# MCU.net
KiCad netlist of a schematic drawn in Altium Designer
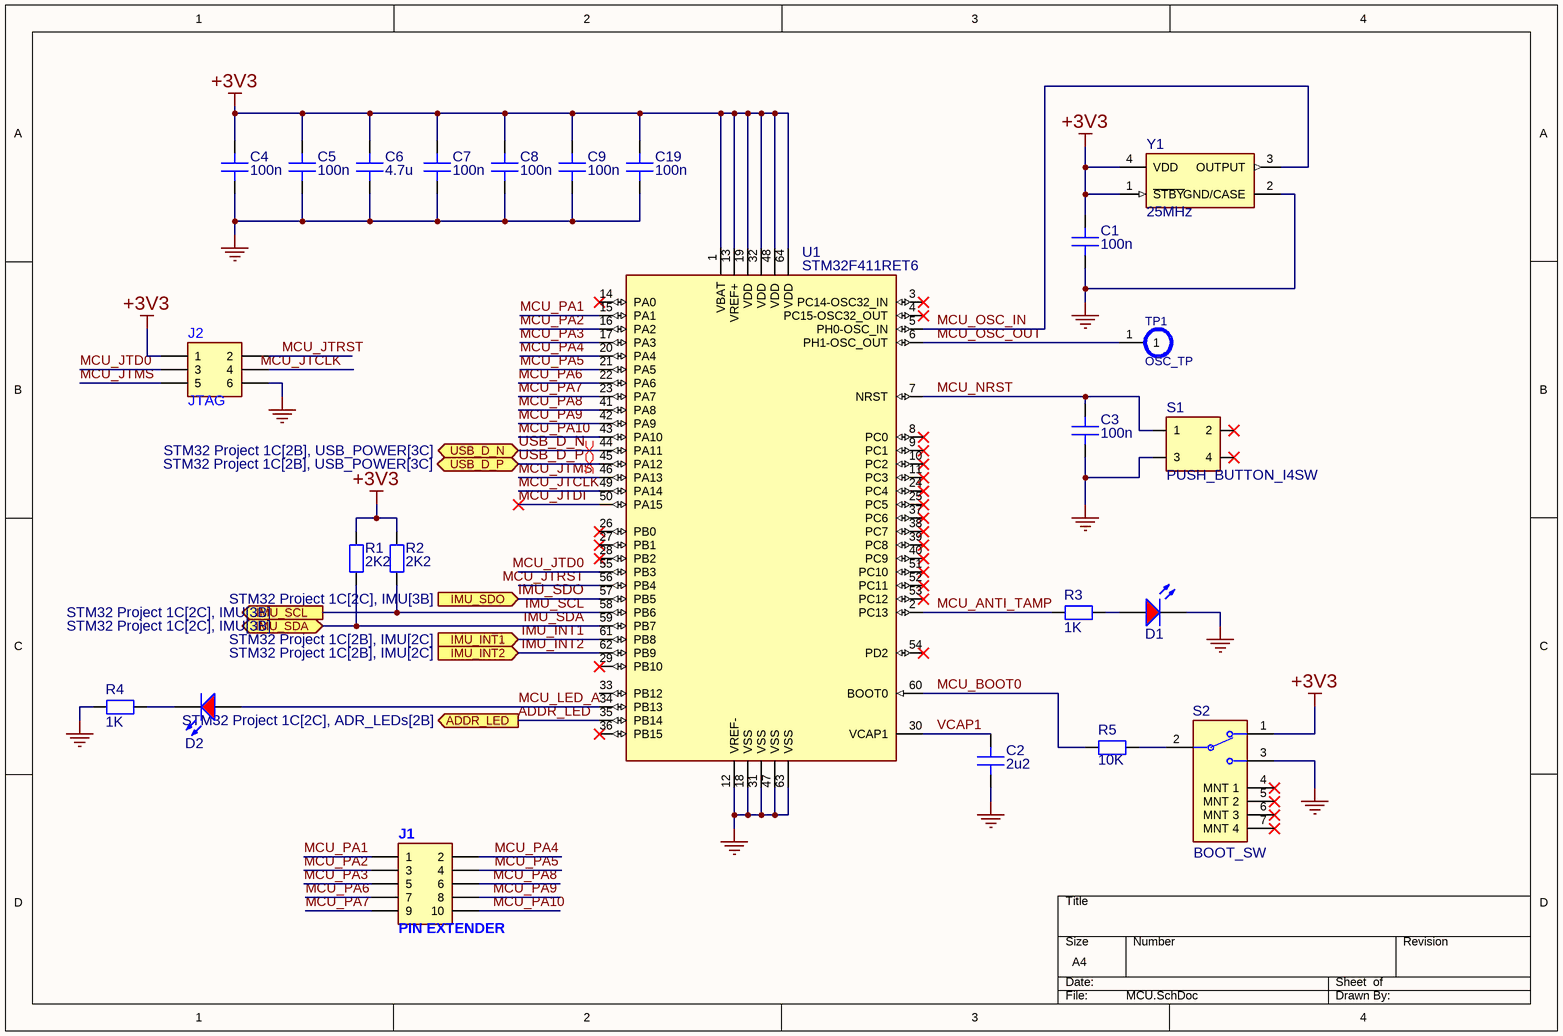
[diagram p0: MCU.SchDoc]

(export (version "E")
  (design (tool "Eeschema 10.0.6"))
  (components
    (comp (ref "C1")
      (value "100n")
      (footprint "CAP_0805")
      (description "Capacitor SMD 0805 Generic")
      (libsource (lib "Generic-Schematic-Library") (part "CAP_0805"))
    )
    (comp (ref "C2")
      (value "2u2")
      (footprint "CAP_0805")
      (description "Capacitor SMD 0805 Generic")
      (libsource (lib "Generic-Schematic-Library") (part "CAP_0805"))
    )
    (comp (ref "C3")
      (value "100n")
      (footprint "CAP_0805")
      (description "Capacitor SMD 0805 Generic")
      (libsource (lib "Generic-Schematic-Library") (part "CAP_0805"))
    )
    (comp (ref "C4")
      (value "100n")
      (footprint "CAP_0805")
      (description "Capacitor SMD 0805 Generic")
      (libsource (lib "Generic-Schematic-Library") (part "CAP_0805"))
    )
    (comp (ref "C5")
      (value "100n")
      (footprint "CAP_0805")
      (description "Capacitor SMD 0805 Generic")
      (libsource (lib "Generic-Schematic-Library") (part "CAP_0805"))
    )
    (comp (ref "C6")
      (value "4.7u")
      (footprint "CAP_0805")
      (description "Capacitor SMD 0805 Generic")
      (libsource (lib "Generic-Schematic-Library") (part "CAP_0805"))
    )
    (comp (ref "C7")
      (value "100n")
      (footprint "CAP_0805")
      (description "Capacitor SMD 0805 Generic")
      (libsource (lib "Generic-Schematic-Library") (part "CAP_0805"))
    )
    (comp (ref "C8")
      (value "100n")
      (footprint "CAP_0805")
      (description "Capacitor SMD 0805 Generic")
      (libsource (lib "Generic-Schematic-Library") (part "CAP_0805"))
    )
    (comp (ref "C9")
      (value "100n")
      (footprint "CAP_0805")
      (description "Capacitor SMD 0805 Generic")
      (libsource (lib "Generic-Schematic-Library") (part "CAP_0805"))
    )
    (comp (ref "C19")
      (value "100n")
      (footprint "CAP_0805")
      (description "Capacitor SMD 0805 Generic")
      (libsource (lib "Generic-Schematic-Library") (part "CAP_0805"))
    )
    (comp (ref "D1")
      (value "LED_RED_0805")
      (footprint "LED_RED_0805")
      (description "Chip LED, Green, 2.2 V, -40 to 85 degC, 2-Pin SMD, Pb-Free, Tape and Reel")
      (libsource (lib "Generic-Schematic-Library") (part "LED_RED_0805"))
    )
    (comp (ref "D2")
      (value "LED_RED_0805")
      (footprint "LED_RED_0805")
      (description "Chip LED, Green, 2.2 V, -40 to 85 degC, 2-Pin SMD, Pb-Free, Tape and Reel")
      (libsource (lib "Generic-Schematic-Library") (part "LED_RED_0805"))
    )
    (comp (ref "J1")
      (value "PIN EXTENDER")
      (footprint "10P_2x5_HEADER")
      (description "10 Position SMD Pin Header 2x5")
      (libsource (lib "Generic-Schematic-Library") (part "10P_2x5_HEADER"))
    )
    (comp (ref "J2")
      (value "JTAG")
      (footprint "6P_2x3_HEADER")
      (description "Male Header, Pitch 2.54 mm, 2 x 3 Position, Height 8.13 mm, -65 to 125 degC, RoHS, Tube")
      (libsource (lib "Generic-Schematic-Library") (part "6P_2x3_HEADER"))
    )
    (comp (ref "R1")
      (value "2K2")
      (footprint "RES_0805")
      (description "Resistor SMD 0805 Generic")
      (libsource (lib "Generic-Schematic-Library") (part "RES_0805"))
    )
    (comp (ref "R2")
      (value "2K2")
      (footprint "RES_0805")
      (description "Resistor SMD 0805 Generic")
      (libsource (lib "Generic-Schematic-Library") (part "RES_0805"))
    )
    (comp (ref "R3")
      (value "1K")
      (footprint "RES_0805")
      (description "Resistor SMD 0805 Generic")
      (libsource (lib "Generic-Schematic-Library") (part "RES_0805"))
    )
    (comp (ref "R4")
      (value "1K")
      (footprint "RES_0805")
      (description "Resistor SMD 0805 Generic")
      (libsource (lib "Generic-Schematic-Library") (part "RES_0805"))
    )
    (comp (ref "R5")
      (value "10K")
      (footprint "RES_0805")
      (description "Resistor SMD 0805 Generic")
      (libsource (lib "Generic-Schematic-Library") (part "RES_0805"))
    )
    (comp (ref "S1")
      (value "PUSH_BUTTON_I4SW")
      (footprint "PUSH_BUTTON_I4SW")
      (libsource (lib "Generic-Schematic-Library") (part "PUSH_BUTTON_I4SW"))
    )
    (comp (ref "S2")
      (value "BOOT_SW")
      (footprint "SLIDE_SWITCH_SPDT")
      (description "SWITCH SLIDE SPDT 300MA 6V")
      (libsource (lib "Generic-Schematic-Library") (part "SLIDE_SWITCH_SPDT"))
    )
    (comp (ref "TP1")
      (value "OSC_TP")
      (footprint "TEST_POINT_SMD")
      (description "Test Point SMD Generic - for in circuit test")
      (libsource (lib "Generic-Schematic-Library") (part "TEST_POINT_SMD"))
    )
    (comp (ref "U1")
      (value "STM32F411RET6")
      (footprint "STM32F411RET6")
      (libsource (lib "Generic-Schematic-Library") (part "STM32F411RET6"))
    )
    (comp (ref "Y1")
      (value "25MHz")
      (footprint "XTAL_OSCILLATOR_25MHz")
      (description "XTAL Oscillator 25MHz ±50ppm CMOS 3.3V 4-SMD 3.2mm x 2.5mm")
      (libsource (lib "Generic-Schematic-Library") (part "XTAL_OSCILLATOR_25MHz"))
    )
  )
  (nets
    (net (code "1") (name "+3V3") (class "Default")
      (node (ref "C1") (pin "2") (pintype "passive"))
      (node (ref "C19") (pin "2") (pintype "passive"))
      (node (ref "C4") (pin "2") (pintype "passive"))
      (node (ref "C5") (pin "2") (pintype "passive"))
      (node (ref "C6") (pin "2") (pintype "passive"))
      (node (ref "C7") (pin "2") (pintype "passive"))
      (node (ref "C8") (pin "2") (pintype "passive"))
      (node (ref "C9") (pin "2") (pintype "passive"))
      (node (ref "J2") (pin "1") (pinfunction "1_1") (pintype "passive"))
      (node (ref "R1") (pin "1") (pintype "passive"))
      (node (ref "R2") (pin "1") (pintype "passive"))
      (node (ref "S2") (pin "1") (pinfunction "1_1") (pintype "passive"))
      (node (ref "U1") (pin "1") (pinfunction "VBAT_1") (pintype "power_in"))
      (node (ref "U1") (pin "13") (pinfunction "VREF+_13") (pintype "power_in"))
      (node (ref "U1") (pin "19") (pinfunction "VDD_19") (pintype "power_in"))
      (node (ref "U1") (pin "32") (pinfunction "VDD_32") (pintype "power_in"))
      (node (ref "U1") (pin "48") (pinfunction "VDD_48") (pintype "power_in"))
      (node (ref "U1") (pin "64") (pinfunction "VDD_64") (pintype "power_in"))
      (node (ref "Y1") (pin "1") (pinfunction "~{STBY}_1") (pintype "input"))
      (node (ref "Y1") (pin "4") (pinfunction "VDD_4") (pintype "power_in"))
    )
    (net (code "2") (name "/ADDR_LED") (class "Default")
      (node (ref "U1") (pin "35") (pinfunction "PB14_35") (pintype "bidirectional"))
    )
    (net (code "3") (name "/IMU_INT1") (class "Default")
      (node (ref "U1") (pin "61") (pinfunction "PB8_61") (pintype "bidirectional"))
    )
    (net (code "4") (name "/IMU_INT2") (class "Default")
      (node (ref "U1") (pin "62") (pinfunction "PB9_62") (pintype "bidirectional"))
    )
    (net (code "5") (name "/IMU_SCL") (class "Default")
      (node (ref "R2") (pin "2") (pintype "passive"))
      (node (ref "U1") (pin "58") (pinfunction "PB6_58") (pintype "bidirectional"))
    )
    (net (code "6") (name "/IMU_SDA") (class "Default")
      (node (ref "R1") (pin "2") (pintype "passive"))
      (node (ref "U1") (pin "59") (pinfunction "PB7_59") (pintype "bidirectional"))
    )
    (net (code "7") (name "/IMU_SDO") (class "Default")
      (node (ref "U1") (pin "57") (pinfunction "PB5_57") (pintype "bidirectional"))
    )
    (net (code "8") (name "/MCU_ANTI_TAMP") (class "Default")
      (node (ref "R3") (pin "1") (pintype "passive"))
      (node (ref "U1") (pin "2") (pinfunction "PC13_2") (pintype "bidirectional"))
    )
    (net (code "9") (name "/MCU_BOOT0") (class "Default")
      (node (ref "R5") (pin "2") (pintype "passive"))
      (node (ref "U1") (pin "60") (pinfunction "BOOT0_60") (pintype "input"))
    )
    (net (code "10") (name "/MCU_JTCLK") (class "Default")
      (node (ref "J2") (pin "4") (pinfunction "4_4") (pintype "passive"))
      (node (ref "U1") (pin "49") (pinfunction "PA14_49") (pintype "bidirectional"))
    )
    (net (code "11") (name "/MCU_JTD0") (class "Default")
      (node (ref "J2") (pin "3") (pinfunction "3_3") (pintype "passive"))
      (node (ref "U1") (pin "55") (pinfunction "PB3_55") (pintype "bidirectional"))
    )
    (net (code "12") (name "/MCU_JTDI") (class "Default")
      (node (ref "U1") (pin "50") (pinfunction "PA15_50") (pintype "bidirectional+no_connect"))
    )
    (net (code "13") (name "/MCU_JTMS") (class "Default")
      (node (ref "J2") (pin "5") (pinfunction "5_5") (pintype "passive"))
      (node (ref "U1") (pin "46") (pinfunction "PA13_46") (pintype "bidirectional"))
    )
    (net (code "14") (name "/MCU_JTRST") (class "Default")
      (node (ref "J2") (pin "2") (pinfunction "2_2") (pintype "passive"))
      (node (ref "U1") (pin "56") (pinfunction "PB4_56") (pintype "bidirectional"))
    )
    (net (code "15") (name "/MCU_LED_A") (class "Default")
      (node (ref "D2") (pin "2") (pinfunction "A_2") (pintype "passive"))
      (node (ref "U1") (pin "34") (pinfunction "PB13_34") (pintype "bidirectional"))
    )
    (net (code "16") (name "/MCU_NRST") (class "Default")
      (node (ref "C3") (pin "2") (pintype "passive"))
      (node (ref "S1") (pin "1") (pinfunction "1_1") (pintype "passive"))
      (node (ref "U1") (pin "7") (pinfunction "NRST_7") (pintype "bidirectional"))
    )
    (net (code "17") (name "/MCU_OSC_IN") (class "Default")
      (node (ref "U1") (pin "5") (pinfunction "PH0-OSC_IN_5") (pintype "bidirectional"))
      (node (ref "Y1") (pin "3") (pinfunction "OUTPUT_3") (pintype "output"))
    )
    (net (code "18") (name "/MCU_OSC_OUT") (class "Default")
      (node (ref "TP1") (pin "1") (pinfunction "1_1") (pintype "passive"))
      (node (ref "U1") (pin "6") (pinfunction "PH1-OSC_OUT_6") (pintype "bidirectional"))
    )
    (net (code "19") (name "/MCU_PA1") (class "Default")
      (node (ref "J1") (pin "1") (pinfunction "1_1") (pintype "passive"))
      (node (ref "U1") (pin "15") (pinfunction "PA1_15") (pintype "bidirectional"))
    )
    (net (code "20") (name "/MCU_PA2") (class "Default")
      (node (ref "J1") (pin "3") (pinfunction "3_3") (pintype "passive"))
      (node (ref "U1") (pin "16") (pinfunction "PA2_16") (pintype "bidirectional"))
    )
    (net (code "21") (name "/MCU_PA3") (class "Default")
      (node (ref "J1") (pin "5") (pinfunction "5_5") (pintype "passive"))
      (node (ref "U1") (pin "17") (pinfunction "PA3_17") (pintype "bidirectional"))
    )
    (net (code "22") (name "/MCU_PA4") (class "Default")
      (node (ref "J1") (pin "2") (pinfunction "2_2") (pintype "passive"))
      (node (ref "U1") (pin "20") (pinfunction "PA4_20") (pintype "bidirectional"))
    )
    (net (code "23") (name "/MCU_PA5") (class "Default")
      (node (ref "J1") (pin "4") (pinfunction "4_4") (pintype "passive"))
      (node (ref "U1") (pin "21") (pinfunction "PA5_21") (pintype "bidirectional"))
    )
    (net (code "24") (name "/MCU_PA6") (class "Default")
      (node (ref "J1") (pin "7") (pinfunction "7_7") (pintype "passive"))
      (node (ref "U1") (pin "22") (pinfunction "PA6_22") (pintype "bidirectional"))
    )
    (net (code "25") (name "/MCU_PA7") (class "Default")
      (node (ref "J1") (pin "9") (pinfunction "9_9") (pintype "passive"))
      (node (ref "U1") (pin "23") (pinfunction "PA7_23") (pintype "bidirectional"))
    )
    (net (code "26") (name "/MCU_PA8") (class "Default")
      (node (ref "J1") (pin "6") (pinfunction "6_6") (pintype "passive"))
      (node (ref "U1") (pin "41") (pinfunction "PA8_41") (pintype "bidirectional"))
    )
    (net (code "27") (name "/MCU_PA9") (class "Default")
      (node (ref "J1") (pin "8") (pinfunction "8_8") (pintype "passive"))
      (node (ref "U1") (pin "42") (pinfunction "PA9_42") (pintype "bidirectional"))
    )
    (net (code "28") (name "/MCU_PA10") (class "Default")
      (node (ref "J1") (pin "10") (pinfunction "10_10") (pintype "passive"))
      (node (ref "U1") (pin "43") (pinfunction "PA10_43") (pintype "bidirectional"))
    )
    (net (code "29") (name "/USB_D_N") (class "Default")
      (node (ref "U1") (pin "44") (pinfunction "PA11_44") (pintype "bidirectional"))
    )
    (net (code "30") (name "/USB_D_P") (class "Default")
      (node (ref "U1") (pin "45") (pinfunction "PA12_45") (pintype "bidirectional"))
    )
    (net (code "31") (name "/VCAP1") (class "Default")
      (node (ref "C2") (pin "2") (pintype "passive"))
      (node (ref "U1") (pin "30") (pinfunction "VCAP1_30") (pintype "passive"))
    )
    (net (code "32") (name "GND") (class "Default")
      (node (ref "C1") (pin "1") (pintype "passive"))
      (node (ref "C19") (pin "1") (pintype "passive"))
      (node (ref "C2") (pin "1") (pintype "passive"))
      (node (ref "C3") (pin "1") (pintype "passive"))
      (node (ref "C4") (pin "1") (pintype "passive"))
      (node (ref "C5") (pin "1") (pintype "passive"))
      (node (ref "C6") (pin "1") (pintype "passive"))
      (node (ref "C7") (pin "1") (pintype "passive"))
      (node (ref "C8") (pin "1") (pintype "passive"))
      (node (ref "C9") (pin "1") (pintype "passive"))
      (node (ref "D1") (pin "1") (pinfunction "K_1") (pintype "passive"))
      (node (ref "J2") (pin "6") (pinfunction "6_6") (pintype "passive"))
      (node (ref "R4") (pin "1") (pintype "passive"))
      (node (ref "S1") (pin "3") (pinfunction "3_3") (pintype "passive"))
      (node (ref "S2") (pin "3") (pinfunction "3_3") (pintype "passive"))
      (node (ref "U1") (pin "12") (pinfunction "VREF-_12") (pintype "power_in"))
      (node (ref "U1") (pin "18") (pinfunction "VSS_18") (pintype "power_in"))
      (node (ref "U1") (pin "31") (pinfunction "VSS_31") (pintype "power_in"))
      (node (ref "U1") (pin "47") (pinfunction "VSS_47") (pintype "power_in"))
      (node (ref "U1") (pin "63") (pinfunction "VSS_63") (pintype "power_in"))
      (node (ref "Y1") (pin "2") (pinfunction "GND/CASE_2") (pintype "power_in"))
    )
    (net (code "33") (name "Net-(D1-A)") (class "Default")
      (node (ref "D1") (pin "2") (pinfunction "A_2") (pintype "passive"))
      (node (ref "R3") (pin "2") (pintype "passive"))
    )
    (net (code "34") (name "Net-(D2-K)") (class "Default")
      (node (ref "D2") (pin "1") (pinfunction "K_1") (pintype "passive"))
      (node (ref "R4") (pin "2") (pintype "passive"))
    )
    (net (code "35") (name "Net-(R5-Pad1)") (class "Default")
      (node (ref "R5") (pin "1") (pintype "passive"))
      (node (ref "S2") (pin "2") (pinfunction "2_2") (pintype "passive"))
    )
    (net (code "36") (name "unconnected-(S1-Pad2)") (class "Default")
      (node (ref "S1") (pin "2") (pinfunction "2_2") (pintype "passive+no_connect"))
    )
    (net (code "37") (name "unconnected-(S1-Pad4)") (class "Default")
      (node (ref "S1") (pin "4") (pinfunction "4_4") (pintype "passive+no_connect"))
    )
    (net (code "38") (name "unconnected-(S2-MNT_1-Pad4)") (class "Default")
      (node (ref "S2") (pin "4") (pinfunction "MNT_1_4") (pintype "passive+no_connect"))
    )
    (net (code "39") (name "unconnected-(S2-MNT_2-Pad5)") (class "Default")
      (node (ref "S2") (pin "5") (pinfunction "MNT_2_5") (pintype "passive+no_connect"))
    )
    (net (code "40") (name "unconnected-(S2-MNT_3-Pad6)") (class "Default")
      (node (ref "S2") (pin "6") (pinfunction "MNT_3_6") (pintype "passive+no_connect"))
    )
    (net (code "41") (name "unconnected-(S2-MNT_4-Pad7)") (class "Default")
      (node (ref "S2") (pin "7") (pinfunction "MNT_4_7") (pintype "passive+no_connect"))
    )
    (net (code "42") (name "unconnected-(U1-PA0-Pad14)") (class "Default")
      (node (ref "U1") (pin "14") (pinfunction "PA0_14") (pintype "bidirectional+no_connect"))
    )
    (net (code "43") (name "unconnected-(U1-PB0-Pad26)") (class "Default")
      (node (ref "U1") (pin "26") (pinfunction "PB0_26") (pintype "bidirectional+no_connect"))
    )
    (net (code "44") (name "unconnected-(U1-PB1-Pad27)") (class "Default")
      (node (ref "U1") (pin "27") (pinfunction "PB1_27") (pintype "bidirectional+no_connect"))
    )
    (net (code "45") (name "unconnected-(U1-PB2-Pad28)") (class "Default")
      (node (ref "U1") (pin "28") (pinfunction "PB2_28") (pintype "bidirectional+no_connect"))
    )
    (net (code "46") (name "unconnected-(U1-PB10-Pad29)") (class "Default")
      (node (ref "U1") (pin "29") (pinfunction "PB10_29") (pintype "bidirectional+no_connect"))
    )
    (net (code "47") (name "unconnected-(U1-PB12-Pad33)") (class "Default")
      (node (ref "U1") (pin "33") (pinfunction "PB12_33") (pintype "bidirectional"))
    )
    (net (code "48") (name "unconnected-(U1-PB15-Pad36)") (class "Default")
      (node (ref "U1") (pin "36") (pinfunction "PB15_36") (pintype "bidirectional+no_connect"))
    )
    (net (code "49") (name "unconnected-(U1-PC0-Pad8)") (class "Default")
      (node (ref "U1") (pin "8") (pinfunction "PC0_8") (pintype "bidirectional+no_connect"))
    )
    (net (code "50") (name "unconnected-(U1-PC1-Pad9)") (class "Default")
      (node (ref "U1") (pin "9") (pinfunction "PC1_9") (pintype "bidirectional+no_connect"))
    )
    (net (code "51") (name "unconnected-(U1-PC2-Pad10)") (class "Default")
      (node (ref "U1") (pin "10") (pinfunction "PC2_10") (pintype "bidirectional+no_connect"))
    )
    (net (code "52") (name "unconnected-(U1-PC3-Pad11)") (class "Default")
      (node (ref "U1") (pin "11") (pinfunction "PC3_11") (pintype "bidirectional+no_connect"))
    )
    (net (code "53") (name "unconnected-(U1-PC4-Pad24)") (class "Default")
      (node (ref "U1") (pin "24") (pinfunction "PC4_24") (pintype "bidirectional+no_connect"))
    )
    (net (code "54") (name "unconnected-(U1-PC5-Pad25)") (class "Default")
      (node (ref "U1") (pin "25") (pinfunction "PC5_25") (pintype "bidirectional+no_connect"))
    )
    (net (code "55") (name "unconnected-(U1-PC6-Pad37)") (class "Default")
      (node (ref "U1") (pin "37") (pinfunction "PC6_37") (pintype "bidirectional+no_connect"))
    )
    (net (code "56") (name "unconnected-(U1-PC7-Pad38)") (class "Default")
      (node (ref "U1") (pin "38") (pinfunction "PC7_38") (pintype "bidirectional+no_connect"))
    )
    (net (code "57") (name "unconnected-(U1-PC8-Pad39)") (class "Default")
      (node (ref "U1") (pin "39") (pinfunction "PC8_39") (pintype "bidirectional+no_connect"))
    )
    (net (code "58") (name "unconnected-(U1-PC9-Pad40)") (class "Default")
      (node (ref "U1") (pin "40") (pinfunction "PC9_40") (pintype "bidirectional+no_connect"))
    )
    (net (code "59") (name "unconnected-(U1-PC10-Pad51)") (class "Default")
      (node (ref "U1") (pin "51") (pinfunction "PC10_51") (pintype "bidirectional+no_connect"))
    )
    (net (code "60") (name "unconnected-(U1-PC11-Pad52)") (class "Default")
      (node (ref "U1") (pin "52") (pinfunction "PC11_52") (pintype "bidirectional+no_connect"))
    )
    (net (code "61") (name "unconnected-(U1-PC12-Pad53)") (class "Default")
      (node (ref "U1") (pin "53") (pinfunction "PC12_53") (pintype "bidirectional+no_connect"))
    )
    (net (code "62") (name "unconnected-(U1-PC14-OSC32_IN-Pad3)") (class "Default")
      (node (ref "U1") (pin "3") (pinfunction "PC14-OSC32_IN_3") (pintype "bidirectional+no_connect"))
    )
    (net (code "63") (name "unconnected-(U1-PC15-OSC32_OUT-Pad4)") (class "Default")
      (node (ref "U1") (pin "4") (pinfunction "PC15-OSC32_OUT_4") (pintype "bidirectional+no_connect"))
    )
    (net (code "64") (name "unconnected-(U1-PD2-Pad54)") (class "Default")
      (node (ref "U1") (pin "54") (pinfunction "PD2_54") (pintype "bidirectional+no_connect"))
    )
  )
)
